# H0FR71.net
KiCad netlist of a schematic drawn in EAGLE
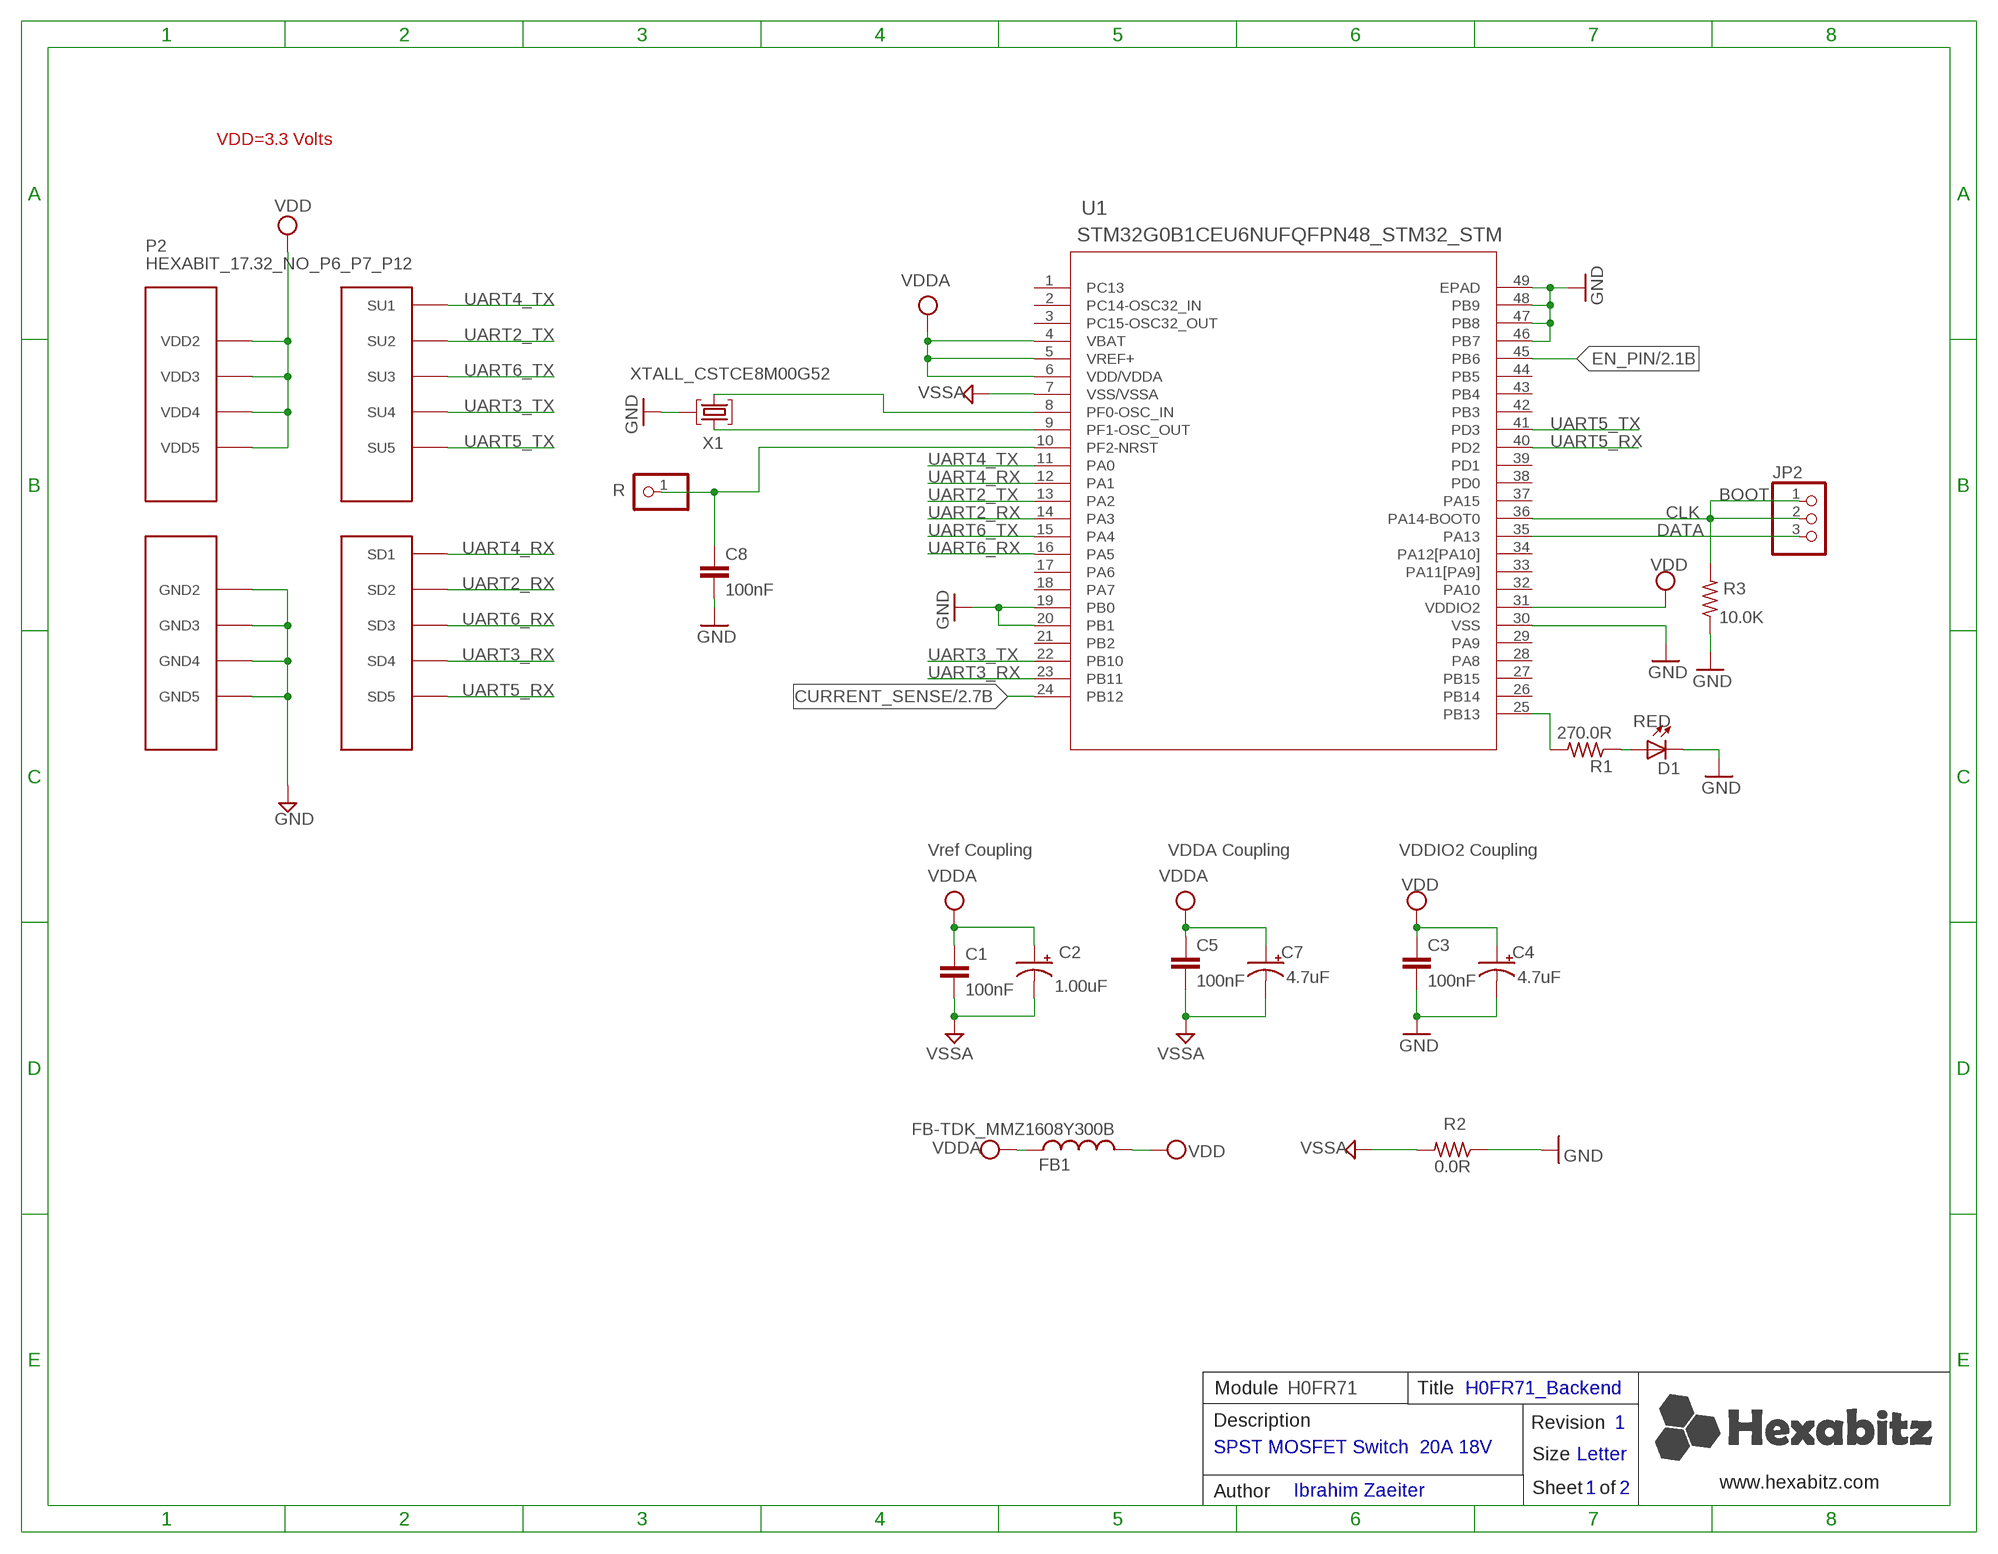
[diagram p0: schematic, sheet 1]
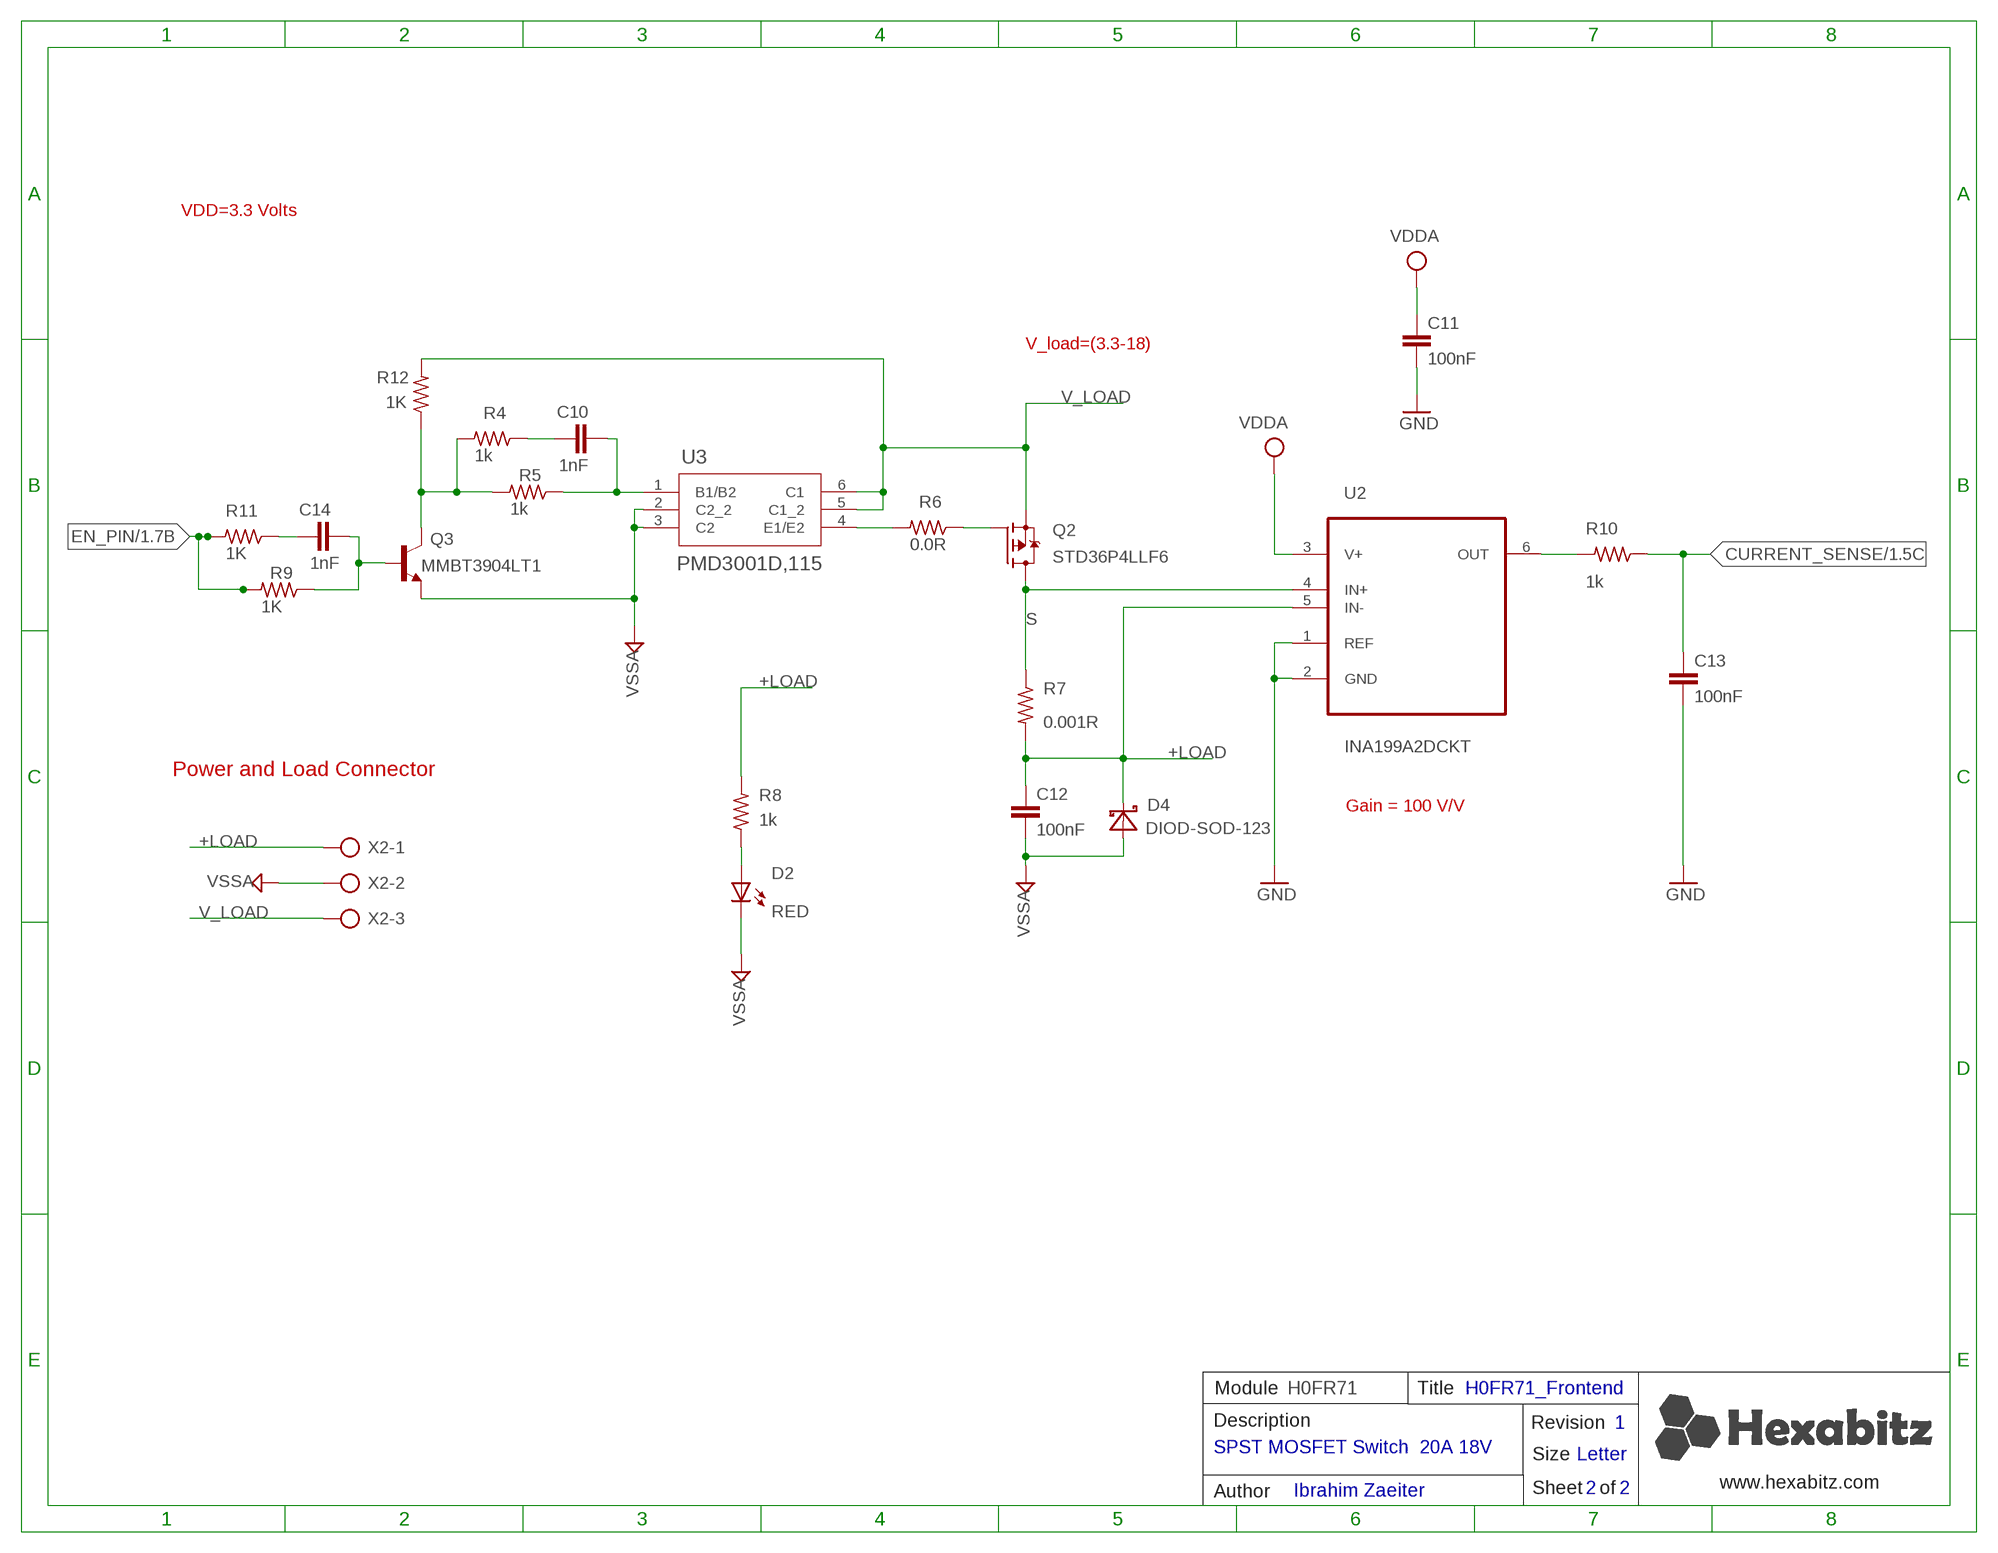
[diagram p1: schematic, sheet 2]

(export (version "E")
  (design (tool "Eeschema 10.0.6"))
  (components
    (comp (ref "C1")
      (value "100nF")
      (footprint "eagle-import:C-0603")
      (fields
        (field (name "CAPACITANCE") "100nF")
        (field (name "MFN") "KEMET")
        (field (name "MPN") "C0603C104K8RACTU")
        (field (name "OCTOPART_URL") "https://octopart.com/c0603c104k8ractu-kemet-145075?r=sp&s=9bS9ASSwSEqMCE9KBEQZ0g")
        (field (name "TOLERANCE") "10%")
        (field (name "VOLTAGE_RATING") "10V")
      )
      (libsource (lib "eagle-import") (part "C-0603"))
    )
    (comp (ref "C2")
      (value "1.00uF")
      (footprint "eagle-import:C-0805-POL")
      (fields
        (field (name "CAPACITANCE") "1.00uF")
        (field (name "MFN") "Yageo")
        (field (name "MPN") "CC0805KKX7R7BB105")
        (field (name "OCTOPART_URL") "https://octopart.com/cc0805kkx7r7bb105-yageo-8376555?r=sp&s=YKl1wwtkROau_X5nniH2ig")
        (field (name "TOLERANCE") "10%")
        (field (name "VOLTAGE_RATING") "16V")
      )
      (libsource (lib "eagle-import") (part "C-0805-POL"))
    )
    (comp (ref "C3")
      (value "100nF")
      (footprint "eagle-import:C-0603")
      (fields
        (field (name "CAPACITANCE") "100nF")
        (field (name "MFN") "KEMET")
        (field (name "MPN") "C0603C104K8RACTU")
        (field (name "OCTOPART_URL") "https://octopart.com/c0603c104k8ractu-kemet-145075?r=sp&s=9bS9ASSwSEqMCE9KBEQZ0g")
        (field (name "TOLERANCE") "10%")
        (field (name "VOLTAGE_RATING") "10V")
      )
      (libsource (lib "eagle-import") (part "C-0603"))
    )
    (comp (ref "C4")
      (value "4.7uF")
      (footprint "eagle-import:C-0805-POL")
      (fields
        (field (name "CAPACITANCE") "4.7uF")
        (field (name "MFN") "Murata")
        (field (name "MPN") "GRM21BC81E475KA12L")
        (field (name "OCTOPART_URL") "https://octopart.com/grm21bc81e475ka12l-murata-10331911?r=sp&s=RY3qZSD8T6mG6TC9CHI5qQ")
        (field (name "TOLERANCE") "10%")
        (field (name "VOLTAGE_RATING") "25V")
      )
      (libsource (lib "eagle-import") (part "C-0805-POL"))
    )
    (comp (ref "C5")
      (value "100nF")
      (footprint "eagle-import:C-0603")
      (fields
        (field (name "CAPACITANCE") "100nF")
        (field (name "MFN") "KEMET")
        (field (name "MPN") "C0603C104K8RACTU")
        (field (name "OCTOPART_URL") "https://octopart.com/c0603c104k8ractu-kemet-145075?r=sp&s=9bS9ASSwSEqMCE9KBEQZ0g")
        (field (name "TOLERANCE") "10%")
        (field (name "VOLTAGE_RATING") "10")
      )
      (libsource (lib "eagle-import") (part "C-0603"))
    )
    (comp (ref "C7")
      (value "4.7uF")
      (footprint "eagle-import:C-0805-POL")
      (fields
        (field (name "CAPACITANCE") "4.7uF")
        (field (name "MFN") "Murata")
        (field (name "MPN") "GRM21BC81E475KA12L")
        (field (name "OCTOPART_URL") "https://octopart.com/grm21bc81e475ka12l-murata-10331911?r=sp&s=RY3qZSD8T6mG6TC9CHI5qQ")
        (field (name "TOLERANCE") "10%")
        (field (name "VOLTAGE_RATING") "25V")
      )
      (libsource (lib "eagle-import") (part "C-0805-POL"))
    )
    (comp (ref "C8")
      (value "100nF")
      (footprint "eagle-import:C-0603")
      (fields
        (field (name "CAPACITANCE") "100nF")
        (field (name "MFN") "KEMET")
        (field (name "MPN") "C0603C104K8RACTU")
        (field (name "OCTOPART_URL") "https://octopart.com/c0603c104k8ractu-kemet-145075?r=sp&s=9bS9ASSwSEqMCE9KBEQZ0g")
        (field (name "TOLERANCE") "10%")
        (field (name "VOLTAGE_RATING") "10V")
      )
      (libsource (lib "eagle-import") (part "C-0603"))
    )
    (comp (ref "D1")
      (value "RED")
      (footprint "eagle-import:VLMS1300-GS08")
      (fields
        (field (name "MPN") "VLMS1300-GS08")
        (field (name "MFN") "Vishay")
        (field (name "MPN_1") "VLMS1300-GS08")
        (field (name "OCTOPART_URL") "https://octopart.com/vlms1300-gs08-vishay-21709201?r=sp&s=_gcP4_q8T1SC6PJQPTQ9yA")
      )
      (libsource (lib "eagle-import") (part "VLMS1300-GS08"))
    )
    (comp (ref "FB1")
      (value "FB-TDK_MMZ1608Y300B")
      (footprint "eagle-import:FB-TDK_MMZ1608Y300B")
      (fields
        (field (name "MFN") "TDK ")
        (field (name "MPN") "MMZ1608Y300B")
        (field (name "OCTOPART_URL") "https://octopart.com/mmz1608y300b-tdk-368280?r=sp&s=cd9_2ZEqQ9q9UNBuQgHAiA")
      )
      (libsource (lib "eagle-import") (part "FB-TDK_MMZ1608Y300B"))
    )
    (comp (ref "JP2")
      (value "PINHD-1X3")
      (footprint "eagle-import:1X03")
      (libsource (lib "eagle-import") (part "PINHD-1X3"))
    )
    (comp (ref "P2")
      (value "HEXABIT_17.32_NO_P6_P7_P12")
      (footprint "eagle-import:HEXABIT_17.32_NO_P6_P7_P12")
      (libsource (lib "eagle-import") (part "HEXABIT_?_NO_P6_P7_P1217.32"))
    )
    (comp (ref "R")
      (value "PINHD-1X1")
      (footprint "eagle-import:1X01")
      (fields (field (name "MPN") "87227-1"))
      (libsource (lib "eagle-import") (part "PINHD-1X1"))
    )
    (comp (ref "R1")
      (value "270.0R")
      (footprint "eagle-import:R-0603")
      (fields
        (field (name "MFN") "Yageo")
        (field (name "MPN") "RC0603FR-07270RL")
        (field (name "OCTOPART_URL") "https://octopart.com/search?q=RC0603FR-07270RL&start=0")
        (field (name "RESISTANCE") "270.0 Ohm")
        (field (name "TOLERANCE") "1%")
      )
      (libsource (lib "eagle-import") (part "R-0603"))
    )
    (comp (ref "R2")
      (value "0.0R")
      (footprint "eagle-import:R-0603")
      (fields
        (field (name "MFN") "Yageo")
        (field (name "MPN") "RC0603JR-070RL")
        (field (name "OCTOPART_URL") "https://octopart.com/rc0603jr-070rl-yageo-1241539?r=sp&s=X2NteqRjRNWrnx42Y0aliA")
        (field (name "RESISTANCE") "0.0 Ohm")
      )
      (libsource (lib "eagle-import") (part "R-0603"))
    )
    (comp (ref "R3")
      (value "10.0K")
      (footprint "eagle-import:R-0603")
      (fields
        (field (name "MFN") "Yageo")
        (field (name "MPN") "RC0603JR-0710KL")
        (field (name "OCTOPART_URL") "https://octopart.com/search?q=RC0603JR-0710KL&start=0")
        (field (name "RESISTANCE") "10.0K Ohm")
        (field (name "TOLERANCE") "5%")
      )
      (libsource (lib "eagle-import") (part "R-0603"))
    )
    (comp (ref "U1")
      (value "STM32G0B1CEU6NUFQFPN48_STM32_STM")
      (footprint "eagle-import:UFQFPN48_STM32_STM")
      (fields
        (field (name "MPN") "STM32G0B1CEU6N")
        (field (name "COPYRIGHT") "Copyright (C) 2022 Ultra Librarian. All rights reserved.")
      )
      (libsource (lib "eagle-import") (part "STM32G0B1CEU6NUFQFPN48_STM32_STM"))
    )
    (comp (ref "X1")
      (value "XTALL_CSTCE8M00G52")
      (footprint "eagle-import:XTALL_CSTCE8M00G52")
      (fields (field (name "MPN") "CSTCE8M00G52Z-R0"))
      (libsource (lib "eagle-import") (part "XTALL_CSTCE8M00G52"))
    )
    (comp (ref "C10")
      (value "1nF")
      (footprint "eagle-import:C-0603")
      (fields
        (field (name "CAPACITANCE") "100nF")
        (field (name "MFN") "KEMET")
        (field (name "MPN") "C0603C104K8RACTU")
        (field (name "OCTOPART_URL") "https://octopart.com/c0603c104k8ractu-kemet-145075?r=sp&s=9bS9ASSwSEqMCE9KBEQZ0g")
        (field (name "TOLERANCE") "10%")
        (field (name "VOLTAGE_RATING") "10V")
      )
      (libsource (lib "eagle-import") (part "C-0603"))
    )
    (comp (ref "C11")
      (value "100nF")
      (footprint "eagle-import:C-0603")
      (fields
        (field (name "CAPACITANCE") "100nF")
        (field (name "MFN") "KEMET")
        (field (name "MPN") "C0603C104K8RACTU")
        (field (name "OCTOPART_URL") "https://octopart.com/c0603c104k8ractu-kemet-145075?r=sp&s=9bS9ASSwSEqMCE9KBEQZ0g")
        (field (name "TOLERANCE") "10V")
        (field (name "VOLTAGE_RATING") "10%")
      )
      (libsource (lib "eagle-import") (part "C-0603"))
    )
    (comp (ref "C12")
      (value "100nF")
      (footprint "eagle-import:C-0603")
      (fields
        (field (name "CAPACITANCE") "100nF")
        (field (name "MFN") "KEMET")
        (field (name "MPN") "C0603C104K8RACTU")
        (field (name "OCTOPART_URL") "https://octopart.com/c0603c104k8ractu-kemet-145075?r=sp&s=9bS9ASSwSEqMCE9KBEQZ0g")
        (field (name "TOLERANCE") "10%")
        (field (name "VOLTAGE_RATING") "10V")
      )
      (libsource (lib "eagle-import") (part "C-0603"))
    )
    (comp (ref "C13")
      (value "100nF")
      (footprint "eagle-import:C-0603")
      (fields
        (field (name "CAPACITANCE") "100nF")
        (field (name "MFN") "KEMET")
        (field (name "MPN") "C0603C104K8RACTU")
        (field (name "OCTOPART_URL") "https://octopart.com/c0603c104k8ractu-kemet-145075?r=sp&s=9bS9ASSwSEqMCE9KBEQZ0g")
        (field (name "TOLERANCE") "10%")
        (field (name "VOLTAGE_RATING") "10V")
      )
      (libsource (lib "eagle-import") (part "C-0603"))
    )
    (comp (ref "C14")
      (value "1nF")
      (footprint "eagle-import:C-0603")
      (fields
        (field (name "CAPACITANCE") "100nF")
        (field (name "MFN") "KEMET")
        (field (name "MPN") "C0603C104K8RACTU")
        (field (name "OCTOPART_URL") "https://octopart.com/c0603c104k8ractu-kemet-145075?r=sp&s=9bS9ASSwSEqMCE9KBEQZ0g")
        (field (name "TOLERANCE") "10%")
        (field (name "VOLTAGE_RATING") "10V")
      )
      (libsource (lib "eagle-import") (part "C-0603"))
    )
    (comp (ref "D2")
      (value "RED")
      (footprint "eagle-import:VLMS1300-GS08")
      (fields
        (field (name "MPN") "VLMS1300-GS08")
        (field (name "MFN") "Vishay")
        (field (name "MPN_1") "VLMO1300-GS08 ")
        (field (name "OCTOPART_URL") "https://octopart.com/vlmo1300-gs08-vishay-21709200?r=sp#")
      )
      (libsource (lib "eagle-import") (part "VLMS1300-GS08"))
    )
    (comp (ref "D4")
      (value "DIOD-SOD-123")
      (footprint "eagle-import:SOD123")
      (libsource (lib "eagle-import") (part "DIOD-SOD-123"))
    )
    (comp (ref "Q2")
      (value "STD36P4LLF6")
      (footprint "eagle-import:DPAK-3")
      (libsource (lib "eagle-import") (part "STD36P4LLF6"))
    )
    (comp (ref "Q3")
      (value "MMBT3904LT1")
      (footprint "eagle-import:MMBT3904LT1")
      (libsource (lib "eagle-import") (part "MMBT3904LT1"))
    )
    (comp (ref "R4")
      (value "1k")
      (footprint "eagle-import:R-0603")
      (fields
        (field (name "MFN") "Yageo")
        (field (name "MPN") "RC0603JR-07680KL")
        (field (name "OCTOPART_URL") "https://octopart.com/rc0603jr-07680kl-yageo-40953169?r=sp")
        (field (name "RESISTANCE") "680K Ohm")
        (field (name "TOLERANCE") "5%")
      )
      (libsource (lib "eagle-import") (part "R-0603"))
    )
    (comp (ref "R5")
      (value "1k")
      (footprint "eagle-import:R-0603")
      (fields
        (field (name "MFN") "Yageo")
        (field (name "MPN") "RC0603JR-07680KL")
        (field (name "OCTOPART_URL") "https://octopart.com/rc0603jr-07680kl-yageo-40953169?r=sp")
        (field (name "RESISTANCE") "680K Ohm")
        (field (name "TOLERANCE") "5%")
      )
      (libsource (lib "eagle-import") (part "R-0603"))
    )
    (comp (ref "R6")
      (value "0.0R")
      (footprint "eagle-import:R-0603")
      (fields
        (field (name "MFN") "Yageo")
        (field (name "MPN") "RC0603JR-070RL")
        (field (name "OCTOPART_URL") "https://octopart.com/rc0603jr-070rl-yageo-1241539?r=sp&s=X2NteqRjRNWrnx42Y0aliA")
        (field (name "RESISTANCE") "0.0 Ohm")
      )
      (libsource (lib "eagle-import") (part "R-0603"))
    )
    (comp (ref "R7")
      (value "0.001R")
      (footprint "eagle-import:R2512")
      (libsource (lib "eagle-import") (part "R-US_R2512"))
    )
    (comp (ref "R8")
      (value "1k")
      (footprint "eagle-import:R-0603")
      (fields
        (field (name "MFN") "Yageo")
        (field (name "MPN") "RC0603JR-071KL")
        (field (name "OCTOPART_URL") "https://octopart.com/rc0603jr-071kl-yageo-55402888?r=sp")
        (field (name "RESISTANCE") "1k")
        (field (name "TOLERANCE") "1%")
      )
      (libsource (lib "eagle-import") (part "R-0603"))
    )
    (comp (ref "R9")
      (value "1K")
      (footprint "eagle-import:R-0603")
      (fields
        (field (name "MFN") "Yageo")
        (field (name "MPN") "RC0603JR-07680KL")
        (field (name "OCTOPART_URL") "https://octopart.com/rc0603jr-07680kl-yageo-40953169?r=sp")
        (field (name "RESISTANCE") "680K Ohm")
        (field (name "TOLERANCE") "5%")
      )
      (libsource (lib "eagle-import") (part "R-0603"))
    )
    (comp (ref "R10")
      (value "1k")
      (footprint "eagle-import:R-0603")
      (fields
        (field (name "MFN") "Yageo")
        (field (name "MPN") "RC0603JR-071KL")
        (field (name "OCTOPART_URL") "https://octopart.com/rc0603jr-071kl-yageo-55402888?r=sp")
        (field (name "RESISTANCE") "1k")
        (field (name "TOLERANCE") "5%")
      )
      (libsource (lib "eagle-import") (part "R-0603"))
    )
    (comp (ref "R11")
      (value "1K")
      (footprint "eagle-import:R-0603")
      (fields
        (field (name "MFN") "Yageo")
        (field (name "MPN") "RC0603JR-07680KL")
        (field (name "OCTOPART_URL") "https://octopart.com/rc0603jr-07680kl-yageo-40953169?r=sp")
        (field (name "RESISTANCE") "680K Ohm")
        (field (name "TOLERANCE") "5%")
      )
      (libsource (lib "eagle-import") (part "R-0603"))
    )
    (comp (ref "R12")
      (value "1K")
      (footprint "eagle-import:R-0603")
      (fields
        (field (name "MFN") "Yageo")
        (field (name "MPN") "RC0603JR-0710KL")
        (field (name "OCTOPART_URL") "https://octopart.com/search?q=RC0603JR-0710KL&start=0")
        (field (name "RESISTANCE") "10.0K Ohm")
        (field (name "TOLERANCE") "5%")
      )
      (libsource (lib "eagle-import") (part "R-0603"))
    )
    (comp (ref "U2")
      (value "INA199A2DCKT")
      (footprint "eagle-import:SOT65P210X110-6N")
      (libsource (lib "eagle-import") (part "INA199A2DCKT"))
    )
    (comp (ref "U3")
      (value "PMD3001D,115")
      (footprint "eagle-import:SOT457_NEX")
      (fields
        (field (name "MANUFACTURER_PART_NUMBER") "PMD3001D")
        (field (name "COPYRIGHT") "Copyright (C) 2022 Ultra Librarian. All rights reserved.")
      )
      (libsource (lib "eagle-import") (part "PMD3001DSOT457_NEX"))
    )
    (comp (ref "X2")
      (value "AK500/3")
      (footprint "eagle-import:AK500_3")
      (libsource (lib "eagle-import") (part "AK500/3"))
    )
  )
  (nets
    (net (code "1") (name "+LOAD") (class "Default")
      (node (ref "C12") (pin "1") (pinfunction "1_1") (pintype "passive"))
      (node (ref "D4") (pin "2") (pinfunction "C_2") (pintype "passive"))
      (node (ref "R7") (pin "2") (pinfunction "2_2") (pintype "passive"))
      (node (ref "R8") (pin "2") (pinfunction "2_2") (pintype "passive"))
      (node (ref "U2") (pin "5") (pinfunction "IN-_5") (pintype "input"))
      (node (ref "X2") (pin "1") (pinfunction "KL_1") (pintype "passive"))
    )
    (net (code "2") (name "AGND") (class "Default")
      (node (ref "C1") (pin "2") (pinfunction "2_2") (pintype "passive"))
      (node (ref "C12") (pin "2") (pinfunction "2_2") (pintype "passive"))
      (node (ref "C2") (pin "2") (pinfunction "-_2") (pintype "passive"))
      (node (ref "C5") (pin "2") (pinfunction "2_2") (pintype "passive"))
      (node (ref "C7") (pin "2") (pinfunction "-_2") (pintype "passive"))
      (node (ref "D2") (pin "C") (pinfunction "C_C") (pintype "passive"))
      (node (ref "D4") (pin "1") (pinfunction "A_1") (pintype "passive"))
      (node (ref "Q3") (pin "2") (pinfunction "E_2") (pintype "passive"))
      (node (ref "R2") (pin "2") (pinfunction "2_2") (pintype "passive"))
      (node (ref "U1") (pin "7") (pinfunction "VSS/VSSA_7") (pintype "passive"))
      (node (ref "U3") (pin "2") (pinfunction "C2_2_2") (pintype "passive"))
      (node (ref "U3") (pin "3") (pinfunction "C2_3") (pintype "passive"))
      (node (ref "X2") (pin "2") (pinfunction "KL_2") (pintype "passive"))
    )
    (net (code "3") (name "CLK") (class "Default")
      (node (ref "JP2") (pin "1") (pinfunction "1_1") (pintype "passive"))
      (node (ref "JP2") (pin "2") (pinfunction "2_2") (pintype "passive"))
      (node (ref "R3") (pin "2") (pinfunction "2_2") (pintype "passive"))
      (node (ref "U1") (pin "36") (pinfunction "PA14-BOOT0_36") (pintype "bidirectional"))
    )
    (net (code "4") (name "CURRENT_SENSE") (class "Default")
      (node (ref "C13") (pin "1") (pinfunction "1_1") (pintype "passive"))
      (node (ref "R10") (pin "1") (pinfunction "1_1") (pintype "passive"))
      (node (ref "U1") (pin "24") (pinfunction "PB12_24") (pintype "bidirectional"))
    )
    (net (code "5") (name "DATA") (class "Default")
      (node (ref "JP2") (pin "3") (pinfunction "3_3") (pintype "passive"))
      (node (ref "U1") (pin "35") (pinfunction "PA13_35") (pintype "bidirectional"))
    )
    (net (code "6") (name "EN_PIN") (class "Default")
      (node (ref "R11") (pin "2") (pinfunction "2_2") (pintype "passive"))
      (node (ref "R9") (pin "2") (pinfunction "2_2") (pintype "passive"))
      (node (ref "U1") (pin "45") (pinfunction "PB6_45") (pintype "bidirectional"))
    )
    (net (code "7") (name "GND") (class "Default")
      (node (ref "C11") (pin "2") (pinfunction "2_2") (pintype "passive"))
      (node (ref "C13") (pin "2") (pinfunction "2_2") (pintype "passive"))
      (node (ref "C3") (pin "2") (pinfunction "2_2") (pintype "passive"))
      (node (ref "C4") (pin "2") (pinfunction "-_2") (pintype "passive"))
      (node (ref "C8") (pin "2") (pinfunction "2_2") (pintype "passive"))
      (node (ref "D1") (pin "C") (pinfunction "C_C") (pintype "passive"))
      (node (ref "P2") (pin "PAD_PD10") (pinfunction "GND4_PAD_PD10") (pintype "power_in"))
      (node (ref "P2") (pin "PAD_PD11") (pinfunction "GND5_PAD_PD11") (pintype "power_in"))
      (node (ref "P2") (pin "PAD_PD8") (pinfunction "GND2_PAD_PD8") (pintype "power_in"))
      (node (ref "P2") (pin "PAD_PD9") (pinfunction "GND3_PAD_PD9") (pintype "power_in"))
      (node (ref "R2") (pin "1") (pinfunction "1_1") (pintype "passive"))
      (node (ref "R3") (pin "1") (pinfunction "1_1") (pintype "passive"))
      (node (ref "U1") (pin "19") (pinfunction "PB0_19") (pintype "bidirectional"))
      (node (ref "U1") (pin "20") (pinfunction "PB1_20") (pintype "bidirectional"))
      (node (ref "U1") (pin "30") (pinfunction "VSS_30") (pintype "passive"))
      (node (ref "U1") (pin "46") (pinfunction "PB7_46") (pintype "bidirectional"))
      (node (ref "U1") (pin "47") (pinfunction "PB8_47") (pintype "bidirectional"))
      (node (ref "U1") (pin "48") (pinfunction "PB9_48") (pintype "bidirectional"))
      (node (ref "U1") (pin "49") (pinfunction "EPAD_49") (pintype "passive"))
      (node (ref "U2") (pin "1") (pinfunction "REF_1") (pintype "input"))
      (node (ref "U2") (pin "2") (pinfunction "GND_2") (pintype "passive"))
      (node (ref "X1") (pin "P$2") (pinfunction "2_P$2") (pintype "passive"))
    )
    (net (code "8") (name "Net-(C10-Pad1)") (class "Default")
      (node (ref "C10") (pin "1") (pinfunction "1_1") (pintype "passive"))
      (node (ref "R4") (pin "1") (pinfunction "1_1") (pintype "passive"))
    )
    (net (code "9") (name "Net-(C14-Pad1)") (class "Default")
      (node (ref "C14") (pin "1") (pinfunction "1_1") (pintype "passive"))
      (node (ref "R11") (pin "1") (pinfunction "1_1") (pintype "passive"))
    )
    (net (code "10") (name "Net-(D1-PadA)") (class "Default")
      (node (ref "D1") (pin "A") (pinfunction "A_A") (pintype "passive"))
      (node (ref "R1") (pin "1") (pinfunction "1_1") (pintype "passive"))
    )
    (net (code "11") (name "Net-(D2-PadA)") (class "Default")
      (node (ref "D2") (pin "A") (pinfunction "A_A") (pintype "passive"))
      (node (ref "R8") (pin "1") (pinfunction "1_1") (pintype "passive"))
    )
    (net (code "12") (name "Net-(Q2-G)") (class "Default")
      (node (ref "Q2") (pin "1") (pinfunction "G_1") (pintype "passive"))
      (node (ref "R6") (pin "1") (pinfunction "1_1") (pintype "passive"))
    )
    (net (code "13") (name "Net-(Q3-B)") (class "Default")
      (node (ref "C14") (pin "2") (pinfunction "2_2") (pintype "passive"))
      (node (ref "Q3") (pin "1") (pinfunction "B_1") (pintype "passive"))
      (node (ref "R9") (pin "1") (pinfunction "1_1") (pintype "passive"))
    )
    (net (code "14") (name "Net-(Q3-C)") (class "Default")
      (node (ref "Q3") (pin "3") (pinfunction "C_3") (pintype "passive"))
      (node (ref "R12") (pin "1") (pinfunction "1_1") (pintype "passive"))
      (node (ref "R4") (pin "2") (pinfunction "2_2") (pintype "passive"))
      (node (ref "R5") (pin "2") (pinfunction "2_2") (pintype "passive"))
    )
    (net (code "15") (name "Net-(U1-PB13)") (class "Default")
      (node (ref "R1") (pin "2") (pinfunction "2_2") (pintype "passive"))
      (node (ref "U1") (pin "25") (pinfunction "PB13_25") (pintype "bidirectional"))
    )
    (net (code "16") (name "Net-(U1-PF0-OSC_IN)") (class "Default")
      (node (ref "U1") (pin "8") (pinfunction "PF0-OSC_IN_8") (pintype "bidirectional"))
      (node (ref "X1") (pin "P$1") (pinfunction "1_P$1") (pintype "passive"))
    )
    (net (code "17") (name "Net-(U1-PF1-OSC_OUT)") (class "Default")
      (node (ref "U1") (pin "9") (pinfunction "PF1-OSC_OUT_9") (pintype "bidirectional"))
      (node (ref "X1") (pin "P$3") (pinfunction "3_P$3") (pintype "passive"))
    )
    (net (code "18") (name "Net-(U1-PF2-NRST)") (class "Default")
      (node (ref "C8") (pin "1") (pinfunction "1_1") (pintype "passive"))
      (node (ref "R") (pin "1") (pinfunction "1_1") (pintype "passive"))
      (node (ref "U1") (pin "10") (pinfunction "PF2-NRST_10") (pintype "bidirectional"))
    )
    (net (code "19") (name "Net-(U2-OUT)") (class "Default")
      (node (ref "R10") (pin "2") (pinfunction "2_2") (pintype "passive"))
      (node (ref "U2") (pin "6") (pinfunction "OUT_6") (pintype "output"))
    )
    (net (code "20") (name "Net-(U3-B1{slash}B2)") (class "Default")
      (node (ref "C10") (pin "2") (pinfunction "2_2") (pintype "passive"))
      (node (ref "R5") (pin "1") (pinfunction "1_1") (pintype "passive"))
      (node (ref "U3") (pin "1") (pinfunction "B1/B2_1") (pintype "passive"))
    )
    (net (code "21") (name "Net-(U3-E1{slash}E2)") (class "Default")
      (node (ref "R6") (pin "2") (pinfunction "2_2") (pintype "passive"))
      (node (ref "U3") (pin "4") (pinfunction "E1/E2_4") (pintype "passive"))
    )
    (net (code "22") (name "S") (class "Default")
      (node (ref "Q2") (pin "4") (pinfunction "D_4") (pintype "passive"))
      (node (ref "R7") (pin "1") (pinfunction "1_1") (pintype "passive"))
      (node (ref "U2") (pin "4") (pinfunction "IN+_4") (pintype "input"))
    )
    (net (code "23") (name "UART2_RX") (class "Default")
      (node (ref "P2") (pin "PAD_PD2") (pinfunction "SD2_PAD_PD2") (pintype "bidirectional"))
      (node (ref "U1") (pin "14") (pinfunction "PA3_14") (pintype "bidirectional"))
    )
    (net (code "24") (name "UART2_TX") (class "Default")
      (node (ref "P2") (pin "PAD_PU2") (pinfunction "SU2_PAD_PU2") (pintype "bidirectional"))
      (node (ref "U1") (pin "13") (pinfunction "PA2_13") (pintype "bidirectional"))
    )
    (net (code "25") (name "UART3_RX") (class "Default")
      (node (ref "P2") (pin "PAD_PD4") (pinfunction "SD4_PAD_PD4") (pintype "bidirectional"))
      (node (ref "U1") (pin "23") (pinfunction "PB11_23") (pintype "bidirectional"))
    )
    (net (code "26") (name "UART3_TX") (class "Default")
      (node (ref "P2") (pin "PAD_PU4") (pinfunction "SU4_PAD_PU4") (pintype "bidirectional"))
      (node (ref "U1") (pin "22") (pinfunction "PB10_22") (pintype "bidirectional"))
    )
    (net (code "27") (name "UART4_RX") (class "Default")
      (node (ref "P2") (pin "PAD_PD1") (pinfunction "SD1_PAD_PD1") (pintype "bidirectional"))
      (node (ref "U1") (pin "12") (pinfunction "PA1_12") (pintype "bidirectional"))
    )
    (net (code "28") (name "UART4_TX") (class "Default")
      (node (ref "P2") (pin "PAD_PU1") (pinfunction "SU1_PAD_PU1") (pintype "bidirectional"))
      (node (ref "U1") (pin "11") (pinfunction "PA0_11") (pintype "bidirectional"))
    )
    (net (code "29") (name "UART5_RX") (class "Default")
      (node (ref "P2") (pin "PAD_PD5") (pinfunction "SD5_PAD_PD5") (pintype "bidirectional"))
      (node (ref "U1") (pin "40") (pinfunction "PD2_40") (pintype "bidirectional"))
    )
    (net (code "30") (name "UART5_TX") (class "Default")
      (node (ref "P2") (pin "PAD_PU5") (pinfunction "SU5_PAD_PU5") (pintype "bidirectional"))
      (node (ref "U1") (pin "41") (pinfunction "PD3_41") (pintype "bidirectional"))
    )
    (net (code "31") (name "UART6_RX") (class "Default")
      (node (ref "P2") (pin "PAD_PD3") (pinfunction "SD3_PAD_PD3") (pintype "bidirectional"))
      (node (ref "U1") (pin "16") (pinfunction "PA5_16") (pintype "bidirectional"))
    )
    (net (code "32") (name "UART6_TX") (class "Default")
      (node (ref "P2") (pin "PAD_PU3") (pinfunction "SU3_PAD_PU3") (pintype "bidirectional"))
      (node (ref "U1") (pin "15") (pinfunction "PA4_15") (pintype "bidirectional"))
    )
    (net (code "33") (name "VDD") (class "Default")
      (node (ref "C3") (pin "1") (pinfunction "1_1") (pintype "passive"))
      (node (ref "C4") (pin "1") (pinfunction "+_1") (pintype "passive"))
      (node (ref "FB1") (pin "2") (pinfunction "2_2") (pintype "passive"))
      (node (ref "P2") (pin "PAD_PU10") (pinfunction "VDD4_PAD_PU10") (pintype "power_in"))
      (node (ref "P2") (pin "PAD_PU11") (pinfunction "VDD5_PAD_PU11") (pintype "power_in"))
      (node (ref "P2") (pin "PAD_PU8") (pinfunction "VDD2_PAD_PU8") (pintype "power_in"))
      (node (ref "P2") (pin "PAD_PU9") (pinfunction "VDD3_PAD_PU9") (pintype "power_in"))
      (node (ref "U1") (pin "31") (pinfunction "VDDIO2_31") (pintype "power_in"))
    )
    (net (code "34") (name "VDDA") (class "Default")
      (node (ref "C1") (pin "1") (pinfunction "1_1") (pintype "passive"))
      (node (ref "C11") (pin "1") (pinfunction "1_1") (pintype "passive"))
      (node (ref "C2") (pin "1") (pinfunction "+_1") (pintype "passive"))
      (node (ref "C5") (pin "1") (pinfunction "1_1") (pintype "passive"))
      (node (ref "C7") (pin "1") (pinfunction "+_1") (pintype "passive"))
      (node (ref "FB1") (pin "1") (pinfunction "1_1") (pintype "passive"))
      (node (ref "U1") (pin "4") (pinfunction "VBAT_4") (pintype "power_in"))
      (node (ref "U1") (pin "5") (pinfunction "VREF+_5") (pintype "power_in"))
      (node (ref "U1") (pin "6") (pinfunction "VDD/VDDA_6") (pintype "power_in"))
      (node (ref "U2") (pin "3") (pinfunction "V+_3") (pintype "power_in"))
    )
    (net (code "35") (name "V_LOAD") (class "Default")
      (node (ref "Q2") (pin "3") (pinfunction "S_3") (pintype "passive"))
      (node (ref "R12") (pin "2") (pinfunction "2_2") (pintype "passive"))
      (node (ref "U3") (pin "5") (pinfunction "C1_2_5") (pintype "passive"))
      (node (ref "U3") (pin "6") (pinfunction "C1_6") (pintype "passive"))
      (node (ref "X2") (pin "3") (pinfunction "KL_3") (pintype "passive"))
    )
    (net (code "36") (name "unconnected-(U1-PA6-Pad17)") (class "Default")
      (node (ref "U1") (pin "17") (pinfunction "PA6_17") (pintype "bidirectional"))
    )
    (net (code "37") (name "unconnected-(U1-PA7-Pad18)") (class "Default")
      (node (ref "U1") (pin "18") (pinfunction "PA7_18") (pintype "bidirectional"))
    )
    (net (code "38") (name "unconnected-(U1-PA8-Pad28)") (class "Default")
      (node (ref "U1") (pin "28") (pinfunction "PA8_28") (pintype "bidirectional"))
    )
    (net (code "39") (name "unconnected-(U1-PA9-Pad29)") (class "Default")
      (node (ref "U1") (pin "29") (pinfunction "PA9_29") (pintype "bidirectional"))
    )
    (net (code "40") (name "unconnected-(U1-PA10-Pad32)") (class "Default")
      (node (ref "U1") (pin "32") (pinfunction "PA10_32") (pintype "bidirectional"))
    )
    (net (code "41") (name "unconnected-(U1-PA11[PA9]-Pad33)") (class "Default")
      (node (ref "U1") (pin "33") (pinfunction "PA11[PA9]_33") (pintype "bidirectional"))
    )
    (net (code "42") (name "unconnected-(U1-PA12[PA10]-Pad34)") (class "Default")
      (node (ref "U1") (pin "34") (pinfunction "PA12[PA10]_34") (pintype "bidirectional"))
    )
    (net (code "43") (name "unconnected-(U1-PA15-Pad37)") (class "Default")
      (node (ref "U1") (pin "37") (pinfunction "PA15_37") (pintype "bidirectional"))
    )
    (net (code "44") (name "unconnected-(U1-PB2-Pad21)") (class "Default")
      (node (ref "U1") (pin "21") (pinfunction "PB2_21") (pintype "bidirectional"))
    )
    (net (code "45") (name "unconnected-(U1-PB3-Pad42)") (class "Default")
      (node (ref "U1") (pin "42") (pinfunction "PB3_42") (pintype "bidirectional"))
    )
    (net (code "46") (name "unconnected-(U1-PB4-Pad43)") (class "Default")
      (node (ref "U1") (pin "43") (pinfunction "PB4_43") (pintype "bidirectional"))
    )
    (net (code "47") (name "unconnected-(U1-PB5-Pad44)") (class "Default")
      (node (ref "U1") (pin "44") (pinfunction "PB5_44") (pintype "bidirectional"))
    )
    (net (code "48") (name "unconnected-(U1-PB14-Pad26)") (class "Default")
      (node (ref "U1") (pin "26") (pinfunction "PB14_26") (pintype "bidirectional"))
    )
    (net (code "49") (name "unconnected-(U1-PB15-Pad27)") (class "Default")
      (node (ref "U1") (pin "27") (pinfunction "PB15_27") (pintype "bidirectional"))
    )
    (net (code "50") (name "unconnected-(U1-PC13-Pad1)") (class "Default")
      (node (ref "U1") (pin "1") (pinfunction "PC13_1") (pintype "bidirectional"))
    )
    (net (code "51") (name "unconnected-(U1-PC14-OSC32_IN-Pad2)") (class "Default")
      (node (ref "U1") (pin "2") (pinfunction "PC14-OSC32_IN_2") (pintype "bidirectional"))
    )
    (net (code "52") (name "unconnected-(U1-PC15-OSC32_OUT-Pad3)") (class "Default")
      (node (ref "U1") (pin "3") (pinfunction "PC15-OSC32_OUT_3") (pintype "bidirectional"))
    )
    (net (code "53") (name "unconnected-(U1-PD0-Pad38)") (class "Default")
      (node (ref "U1") (pin "38") (pinfunction "PD0_38") (pintype "bidirectional"))
    )
    (net (code "54") (name "unconnected-(U1-PD1-Pad39)") (class "Default")
      (node (ref "U1") (pin "39") (pinfunction "PD1_39") (pintype "bidirectional"))
    )
  )
)
